# Powerbank.net
KiCad netlist of a schematic drawn in EAGLE
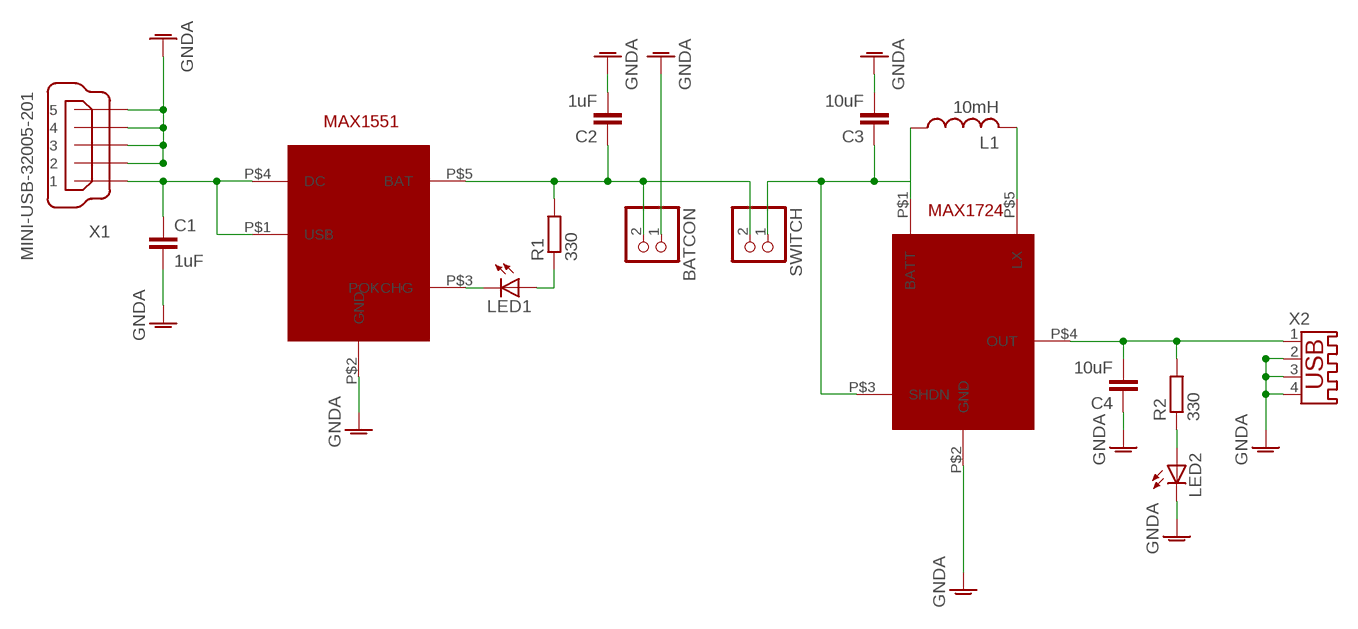
[diagram p0: schematic, sheet 1]

(export (version "E")
  (design (tool "Eeschema 10.0.6"))
  (components
    (comp (ref "BATCON")
      (value "PINHD-1X2")
      (footprint "eagle-import:1X02")
      (libsource (lib "eagle-import") (part "PINHD-1X2"))
    )
    (comp (ref "C1")
      (value "1uF")
      (footprint "eagle-import:C0805")
      (libsource (lib "eagle-import") (part "C-EUC0805"))
    )
    (comp (ref "C2")
      (value "1uF")
      (footprint "eagle-import:C0805")
      (libsource (lib "eagle-import") (part "C-EUC0805"))
    )
    (comp (ref "C3")
      (value "10uF")
      (footprint "eagle-import:C0805")
      (libsource (lib "eagle-import") (part "C-EUC0805"))
    )
    (comp (ref "C4")
      (value "10uF")
      (footprint "eagle-import:C0805")
      (libsource (lib "eagle-import") (part "C-EUC0805"))
    )
    (comp (ref "L1")
      (value "10mH")
      (footprint "eagle-import:L3216C")
      (libsource (lib "eagle-import") (part "L-USL3216C"))
    )
    (comp (ref "LED1")
      (value "LEDCHIP-LED0805")
      (footprint "eagle-import:CHIP-LED0805")
      (libsource (lib "eagle-import") (part "LEDCHIP-LED0805"))
    )
    (comp (ref "LED2")
      (value "LEDCHIP-LED0805")
      (footprint "eagle-import:CHIP-LED0805")
      (libsource (lib "eagle-import") (part "LEDCHIP-LED0805"))
    )
    (comp (ref "R1")
      (value "330")
      (footprint "eagle-import:R0805")
      (libsource (lib "eagle-import") (part "R-EU_R0805"))
    )
    (comp (ref "R2")
      (value "330")
      (footprint "eagle-import:R0805")
      (libsource (lib "eagle-import") (part "R-EU_R0805"))
    )
    (comp (ref "SWITCH")
      (value "PINHD-1X2")
      (footprint "eagle-import:1X02")
      (libsource (lib "eagle-import") (part "PINHD-1X2"))
    )
    (comp (ref "U$1")
      (value "MAX1551")
      (footprint "eagle-import:SOT23")
      (libsource (lib "eagle-import") (part "MAX1551"))
    )
    (comp (ref "U$2")
      (value "MAX1724")
      (footprint "eagle-import:SOT23")
      (libsource (lib "eagle-import") (part "MAX1724"))
    )
    (comp (ref "X1")
      (value "MINI-USB-32005-201")
      (footprint "eagle-import:32005-201")
      (libsource (lib "eagle-import") (part "MINI-USB-32005-201"))
    )
    (comp (ref "X2")
      (value "USB-A003")
      (footprint "eagle-import:USB-A003")
      (libsource (lib "eagle-import") (part "USB-A003"))
    )
  )
  (nets
    (net (code "1") (name "GNDA") (class "Default")
      (node (ref "BATCON") (pin "1") (pinfunction "1_1") (pintype "passive"))
      (node (ref "C1") (pin "2") (pinfunction "2_2") (pintype "passive"))
      (node (ref "C2") (pin "2") (pinfunction "2_2") (pintype "passive"))
      (node (ref "C3") (pin "2") (pinfunction "2_2") (pintype "passive"))
      (node (ref "C4") (pin "1") (pinfunction "1_1") (pintype "passive"))
      (node (ref "LED2") (pin "C") (pinfunction "C_C") (pintype "passive"))
      (node (ref "U$1") (pin "P$2") (pinfunction "GND_P$2") (pintype "input"))
      (node (ref "U$2") (pin "P$2") (pinfunction "GND_P$2") (pintype "input"))
      (node (ref "X1") (pin "2") (pinfunction "2_2") (pintype "passive"))
      (node (ref "X1") (pin "3") (pinfunction "3_3") (pintype "passive"))
      (node (ref "X1") (pin "4") (pinfunction "4_4") (pintype "passive"))
      (node (ref "X1") (pin "5") (pinfunction "5_5") (pintype "passive"))
      (node (ref "X2") (pin "2") (pinfunction "2_2") (pintype "passive"))
      (node (ref "X2") (pin "3") (pinfunction "3_3") (pintype "passive"))
      (node (ref "X2") (pin "4") (pinfunction "4_4") (pintype "passive"))
    )
    (net (code "2") (name "Net-(LED1-PadA)") (class "Default")
      (node (ref "LED1") (pin "A") (pinfunction "A_A") (pintype "passive"))
      (node (ref "R1") (pin "1") (pinfunction "1_1") (pintype "passive"))
    )
    (net (code "3") (name "Net-(LED2-PadA)") (class "Default")
      (node (ref "LED2") (pin "A") (pinfunction "A_A") (pintype "passive"))
      (node (ref "R2") (pin "1") (pinfunction "1_1") (pintype "passive"))
    )
    (net (code "4") (name "Net-(U$1-BAT)") (class "Default")
      (node (ref "BATCON") (pin "2") (pinfunction "2_2") (pintype "passive"))
      (node (ref "C2") (pin "1") (pinfunction "1_1") (pintype "passive"))
      (node (ref "R1") (pin "2") (pinfunction "2_2") (pintype "passive"))
      (node (ref "SWITCH") (pin "2") (pinfunction "2_2") (pintype "passive"))
      (node (ref "U$1") (pin "P$5") (pinfunction "BAT_P$5") (pintype "bidirectional"))
    )
    (net (code "5") (name "Net-(U$1-DC)") (class "Default")
      (node (ref "C1") (pin "1") (pinfunction "1_1") (pintype "passive"))
      (node (ref "U$1") (pin "P$1") (pinfunction "USB_P$1") (pintype "bidirectional"))
      (node (ref "U$1") (pin "P$4") (pinfunction "DC_P$4") (pintype "bidirectional"))
      (node (ref "X1") (pin "1") (pinfunction "1_1") (pintype "passive"))
    )
    (net (code "6") (name "Net-(U$1-POKCHG)") (class "Default")
      (node (ref "LED1") (pin "C") (pinfunction "C_C") (pintype "passive"))
      (node (ref "U$1") (pin "P$3") (pinfunction "POKCHG_P$3") (pintype "input"))
    )
    (net (code "7") (name "Net-(U$2-BATT)") (class "Default")
      (node (ref "C3") (pin "1") (pinfunction "1_1") (pintype "passive"))
      (node (ref "L1") (pin "1") (pinfunction "1_1") (pintype "passive"))
      (node (ref "SWITCH") (pin "1") (pinfunction "1_1") (pintype "passive"))
      (node (ref "U$2") (pin "P$1") (pinfunction "BATT_P$1") (pintype "bidirectional"))
      (node (ref "U$2") (pin "P$3") (pinfunction "SHDN_P$3") (pintype "input"))
    )
    (net (code "8") (name "Net-(U$2-LX)") (class "Default")
      (node (ref "L1") (pin "2") (pinfunction "2_2") (pintype "passive"))
      (node (ref "U$2") (pin "P$5") (pinfunction "LX_P$5") (pintype "bidirectional"))
    )
    (net (code "9") (name "Net-(U$2-OUT)") (class "Default")
      (node (ref "C4") (pin "2") (pinfunction "2_2") (pintype "passive"))
      (node (ref "R2") (pin "2") (pinfunction "2_2") (pintype "passive"))
      (node (ref "U$2") (pin "P$4") (pinfunction "OUT_P$4") (pintype "bidirectional"))
      (node (ref "X2") (pin "1") (pinfunction "1_1") (pintype "passive"))
    )
  )
)
